# UART_1.net
KiCad netlist of a schematic drawn in Altium Designer
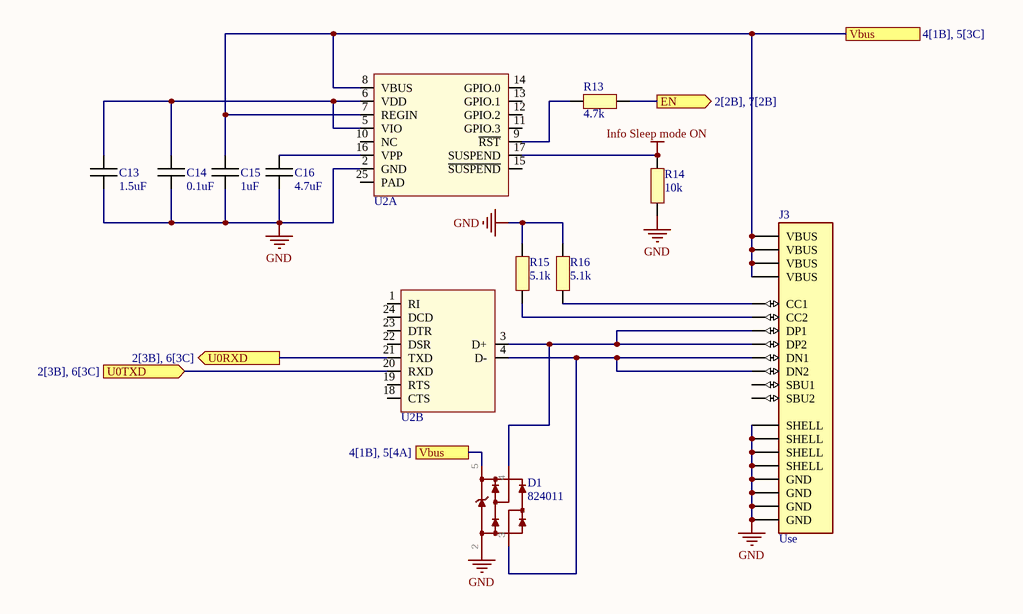
[diagram p0: UART 1.SchDoc]

(export (version "E")
  (design (tool "Eeschema 10.0.6"))
  (components
    (comp (ref "C13")
      (value "1.5uF")
      (footprint "CAPC1005X06N")
      (libsource (lib "SCHLibrary") (part "Capacitor"))
    )
    (comp (ref "C14")
      (value "0.1uF")
      (footprint "CAPC1005X06N")
      (libsource (lib "SCHLibrary") (part "Capacitor"))
    )
    (comp (ref "C15")
      (value "1uF")
      (footprint "CAPC1005X06N")
      (libsource (lib "SCHLibrary") (part "Capacitor"))
    )
    (comp (ref "C16")
      (value "4.7uF")
      (footprint "CAPC1005X06N")
      (libsource (lib "SCHLibrary") (part "Capacitor"))
    )
    (comp (ref "D1") (value "824011") (footprint "824011") (libsource (lib "SCHLibrary") (part "824011")))
    (comp (ref "J3")
      (value "Use")
      (footprint "USB4085-GF-A")
      (description "Connecteurs USB USB Type C, 2.0, Rec, TH , G/F, RA , Top Mnt, T & R")
      (libsource (lib "SCHLibrary") (part "USB4085-GF-A"))
    )
    (comp (ref "R13") (value "4.7k") (footprint "RESC1005X06N") (libsource (lib "") (part "Resistor_1")))
    (comp (ref "R14")
      (value "10k")
      (footprint "RESC1005X06N")
      (libsource (lib "SCHLibrary") (part "Resistor"))
    )
    (comp (ref "R15") (value "5.1k") (footprint "RESC1005X06N") (libsource (lib "") (part "Resistor_2")))
    (comp (ref "R16") (value "5.1k") (footprint "RESC1005X06N") (libsource (lib "") (part "Resistor_2")))
    (comp (ref "U2")
      (value "CP2104-F03-GM")
      (footprint "PQFN50P400X400X80_HS-25N")
      (description "USB Bridge, USB to UART USB 2.0 UART Interface 24-QFN (4x4)")
      (libsource (lib "SCHLibrary") (part "USBBridge"))
    )
  )
  (nets
    (net (code "1") (name "/EN") (class "Default")
      (node (ref "R13") (pin "1") (pinfunction "1_1") (pintype "passive"))
    )
    (net (code "2") (name "/U0RXD") (class "Default")
      (node (ref "U2") (pin "21") (pinfunction "TXD_21") (pintype "passive"))
    )
    (net (code "3") (name "/U0TXD") (class "Default")
      (node (ref "U2") (pin "20") (pinfunction "RXD_20") (pintype "passive"))
    )
    (net (code "4") (name "/Vbus") (class "Default")
      (node (ref "C15") (pin "1") (pinfunction "1_1") (pintype "passive"))
      (node (ref "D1") (pin "5") (pinfunction "VDD_5") (pintype "power_in"))
      (node (ref "J3") (pin "A4") (pinfunction "VBUS_A4") (pintype "power_in"))
      (node (ref "J3") (pin "A9") (pinfunction "VBUS_A9") (pintype "power_in"))
      (node (ref "J3") (pin "B4") (pinfunction "VBUS_B4") (pintype "power_in"))
      (node (ref "J3") (pin "B9") (pinfunction "VBUS_B9") (pintype "power_in"))
      (node (ref "U2") (pin "7") (pinfunction "REGIN_7") (pintype "passive"))
      (node (ref "U2") (pin "8") (pinfunction "VBUS_8") (pintype "passive"))
    )
    (net (code "5") (name "GND") (class "Default")
      (node (ref "C13") (pin "2") (pinfunction "2_2") (pintype "passive"))
      (node (ref "C14") (pin "2") (pinfunction "2_2") (pintype "passive"))
      (node (ref "C15") (pin "2") (pinfunction "2_2") (pintype "passive"))
      (node (ref "C16") (pin "2") (pinfunction "2_2") (pintype "passive"))
      (node (ref "D1") (pin "2") (pinfunction "GND_2") (pintype "power_in"))
      (node (ref "J3") (pin "A1") (pinfunction "GND_A1") (pintype "power_in"))
      (node (ref "J3") (pin "A12") (pinfunction "GND_A12") (pintype "power_in"))
      (node (ref "J3") (pin "B1") (pinfunction "GND_B1") (pintype "power_in"))
      (node (ref "J3") (pin "B12") (pinfunction "GND_B12") (pintype "power_in"))
      (node (ref "J3") (pin "S1") (pinfunction "SHELL_S1") (pintype "passive"))
      (node (ref "J3") (pin "S2") (pinfunction "SHELL_S2") (pintype "passive"))
      (node (ref "J3") (pin "S3") (pinfunction "SHELL_S3") (pintype "passive"))
      (node (ref "J3") (pin "S4") (pinfunction "SHELL_S4") (pintype "passive"))
      (node (ref "R14") (pin "2") (pinfunction "2_2") (pintype "passive"))
      (node (ref "R15") (pin "2") (pinfunction "2_2") (pintype "passive"))
      (node (ref "R16") (pin "2") (pinfunction "2_2") (pintype "passive"))
      (node (ref "U2") (pin "2") (pinfunction "GND_2") (pintype "passive"))
    )
    (net (code "6") (name "Info Sleep mode ON") (class "Default")
      (node (ref "R14") (pin "1") (pinfunction "1_1") (pintype "passive"))
      (node (ref "U2") (pin "17") (pinfunction "SUSPEND_17") (pintype "passive"))
    )
    (net (code "7") (name "Net-(D1-1)") (class "Default")
      (node (ref "D1") (pin "3") (pinfunction "1_3") (pintype "passive"))
      (node (ref "J3") (pin "A7") (pinfunction "DN1_A7") (pintype "bidirectional"))
      (node (ref "J3") (pin "B7") (pinfunction "DN2_B7") (pintype "bidirectional"))
      (node (ref "U2") (pin "4") (pinfunction "D-_4") (pintype "passive"))
    )
    (net (code "8") (name "Net-(D1-2)") (class "Default")
      (node (ref "D1") (pin "4") (pinfunction "2_4") (pintype "passive"))
      (node (ref "J3") (pin "A6") (pinfunction "DP1_A6") (pintype "bidirectional"))
      (node (ref "J3") (pin "B6") (pinfunction "DP2_B6") (pintype "bidirectional"))
      (node (ref "U2") (pin "3") (pinfunction "D+_3") (pintype "passive"))
    )
    (net (code "9") (name "Net-(J3-CC1)") (class "Default")
      (node (ref "J3") (pin "A5") (pinfunction "CC1_A5") (pintype "bidirectional"))
      (node (ref "R16") (pin "1") (pinfunction "1_1") (pintype "passive"))
    )
    (net (code "10") (name "Net-(J3-CC2)") (class "Default")
      (node (ref "J3") (pin "B5") (pinfunction "CC2_B5") (pintype "bidirectional"))
      (node (ref "R15") (pin "1") (pinfunction "1_1") (pintype "passive"))
    )
    (net (code "11") (name "Net-(U2A-VDD)") (class "Default")
      (node (ref "C13") (pin "1") (pinfunction "1_1") (pintype "passive"))
      (node (ref "C14") (pin "1") (pinfunction "1_1") (pintype "passive"))
      (node (ref "U2") (pin "5") (pinfunction "VIO_5") (pintype "passive"))
      (node (ref "U2") (pin "6") (pinfunction "VDD_6") (pintype "passive"))
    )
    (net (code "12") (name "Net-(U2A-VPP)") (class "Default")
      (node (ref "C16") (pin "1") (pinfunction "1_1") (pintype "passive"))
      (node (ref "U2") (pin "16") (pinfunction "VPP_16") (pintype "passive"))
    )
    (net (code "13") (name "Net-(U2A-~{RST})") (class "Default")
      (node (ref "R13") (pin "2") (pinfunction "2_2") (pintype "passive"))
      (node (ref "U2") (pin "9") (pinfunction "~{RST}_9") (pintype "passive"))
    )
    (net (code "14") (name "unconnected-(J3-SBU1-PadA8)") (class "Default")
      (node (ref "J3") (pin "A8") (pinfunction "SBU1_A8") (pintype "bidirectional"))
    )
    (net (code "15") (name "unconnected-(J3-SBU2-PadB8)") (class "Default")
      (node (ref "J3") (pin "B8") (pinfunction "SBU2_B8") (pintype "bidirectional"))
    )
    (net (code "16") (name "unconnected-(U2A-GPIO.0-Pad14)") (class "Default")
      (node (ref "U2") (pin "14") (pinfunction "GPIO.0_14") (pintype "passive"))
    )
    (net (code "17") (name "unconnected-(U2A-GPIO.1-Pad13)") (class "Default")
      (node (ref "U2") (pin "13") (pinfunction "GPIO.1_13") (pintype "passive"))
    )
    (net (code "18") (name "unconnected-(U2A-GPIO.2-Pad12)") (class "Default")
      (node (ref "U2") (pin "12") (pinfunction "GPIO.2_12") (pintype "passive"))
    )
    (net (code "19") (name "unconnected-(U2A-GPIO.3-Pad11)") (class "Default")
      (node (ref "U2") (pin "11") (pinfunction "GPIO.3_11") (pintype "passive"))
    )
    (net (code "20") (name "unconnected-(U2A-NC-Pad10)") (class "Default")
      (node (ref "U2") (pin "10") (pinfunction "NC_10") (pintype "passive"))
    )
    (net (code "21") (name "unconnected-(U2A-PAD-Pad25)") (class "Default")
      (node (ref "U2") (pin "25") (pinfunction "PAD_25") (pintype "passive"))
    )
    (net (code "22") (name "unconnected-(U2A-~{SUSPEND}-Pad15)") (class "Default")
      (node (ref "U2") (pin "15") (pinfunction "~{SUSPEND}_15") (pintype "passive"))
    )
    (net (code "23") (name "unconnected-(U2B-CTS-Pad18)") (class "Default")
      (node (ref "U2") (pin "18") (pinfunction "CTS_18") (pintype "passive"))
    )
    (net (code "24") (name "unconnected-(U2B-DCD-Pad24)") (class "Default")
      (node (ref "U2") (pin "24") (pinfunction "DCD_24") (pintype "passive"))
    )
    (net (code "25") (name "unconnected-(U2B-DSR-Pad22)") (class "Default")
      (node (ref "U2") (pin "22") (pinfunction "DSR_22") (pintype "passive"))
    )
    (net (code "26") (name "unconnected-(U2B-DTR-Pad23)") (class "Default")
      (node (ref "U2") (pin "23") (pinfunction "DTR_23") (pintype "passive"))
    )
    (net (code "27") (name "unconnected-(U2B-RI-Pad1)") (class "Default")
      (node (ref "U2") (pin "1") (pinfunction "RI_1") (pintype "passive"))
    )
    (net (code "28") (name "unconnected-(U2B-RTS-Pad19)") (class "Default")
      (node (ref "U2") (pin "19") (pinfunction "RTS_19") (pintype "passive"))
    )
  )
)
